# teclado_at_f343_smd_v2.net
KiCad netlist of a schematic drawn in EAGLE
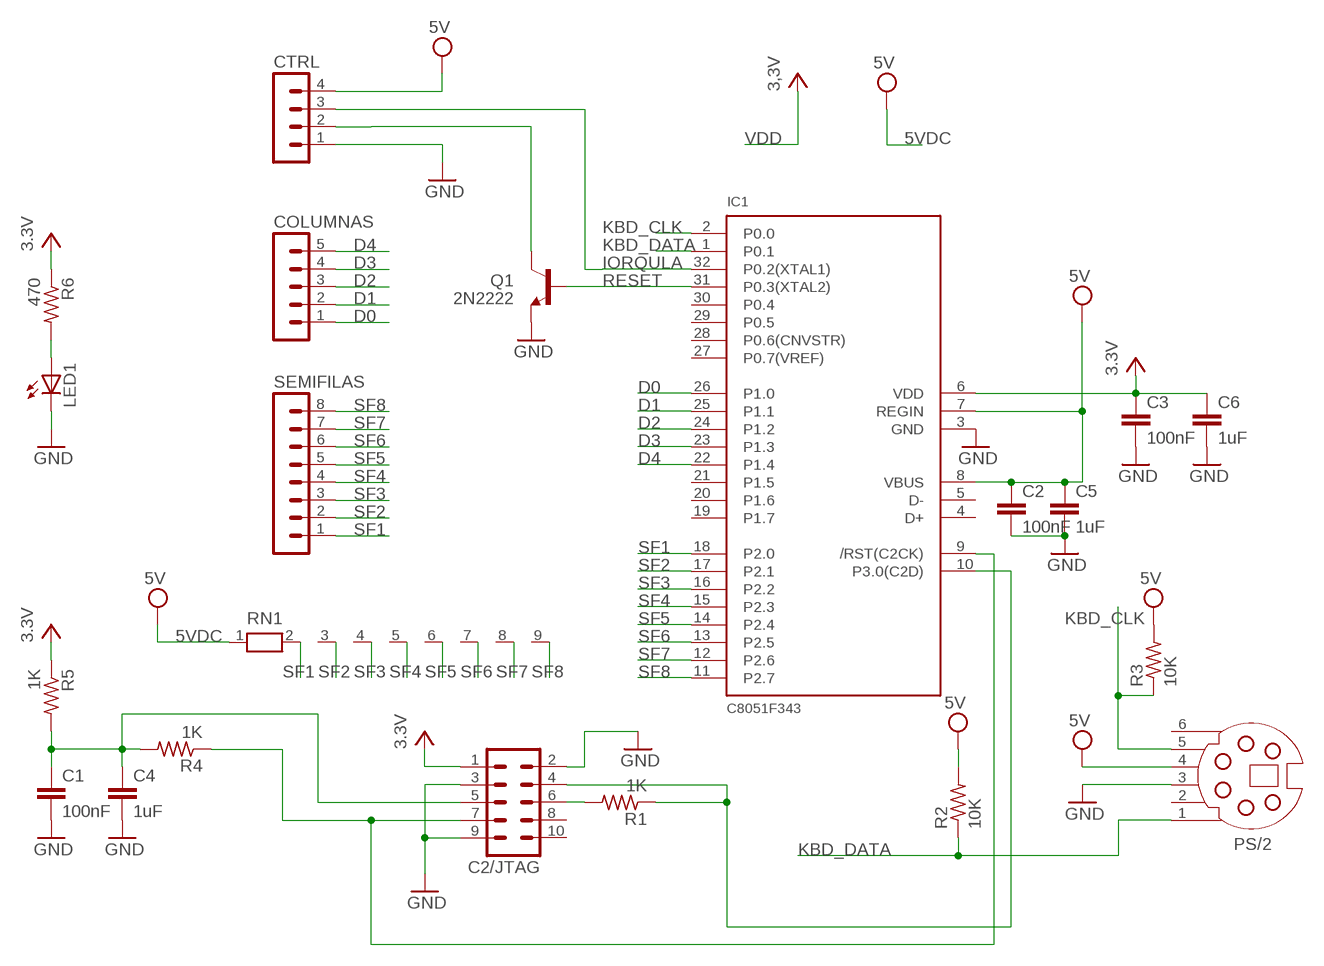
[diagram p0: schematic, sheet 1]

(export (version "E")
  (design (tool "Eeschema 10.0.6"))
  (components
    (comp (ref "C1")
      (value "100nF")
      (footprint "eagle-import:C0805K")
      (libsource (lib "eagle-import") (part "C-EUC0805K"))
    )
    (comp (ref "C2")
      (value "100nF")
      (footprint "eagle-import:C0805K")
      (libsource (lib "eagle-import") (part "C-EUC0805K"))
    )
    (comp (ref "C2/JTAG")
      (value "MA05-2")
      (footprint "eagle-import:MA05-2")
      (libsource (lib "eagle-import") (part "MA05-2"))
    )
    (comp (ref "C3")
      (value "100nF")
      (footprint "eagle-import:C0805K")
      (libsource (lib "eagle-import") (part "C-EUC0805K"))
    )
    (comp (ref "C4")
      (value "1uF")
      (footprint "eagle-import:C0805K")
      (libsource (lib "eagle-import") (part "C-EUC0805K"))
    )
    (comp (ref "C5")
      (value "1uF")
      (footprint "eagle-import:C0805K")
      (libsource (lib "eagle-import") (part "C-EUC0805K"))
    )
    (comp (ref "C6")
      (value "1uF")
      (footprint "eagle-import:C0805K")
      (libsource (lib "eagle-import") (part "C-EUC0805K"))
    )
    (comp (ref "COLUMNAS")
      (value "MA05-1")
      (footprint "eagle-import:MA05-1")
      (libsource (lib "eagle-import") (part "MA05-1"))
    )
    (comp (ref "CTRL")
      (value "MA04-1")
      (footprint "eagle-import:MA04-1")
      (libsource (lib "eagle-import") (part "MA04-1"))
    )
    (comp (ref "IC1")
      (value "C8051F343")
      (footprint "eagle-import:TQFP32-08")
      (libsource (lib "eagle-import") (part "C8051F343"))
    )
    (comp (ref "LED1")
      (value "LEDCHIP-LED0805")
      (footprint "eagle-import:CHIP-LED0805")
      (libsource (lib "eagle-import") (part "LEDCHIP-LED0805"))
    )
    (comp (ref "PS/2")
      (value "SSV-G06")
      (footprint "eagle-import:SSV-BC06")
      (libsource (lib "eagle-import") (part "SSV-G06"))
    )
    (comp (ref "Q1")
      (value "2N2222")
      (footprint "eagle-import:SOT23-3")
      (libsource (lib "eagle-import") (part "TRANSISTOR_NPNSOT23-3"))
    )
    (comp (ref "R1")
      (value "1K")
      (footprint "eagle-import:M0805")
      (libsource (lib "eagle-import") (part "R-US_M0805"))
    )
    (comp (ref "R2")
      (value "10K")
      (footprint "eagle-import:M0805")
      (libsource (lib "eagle-import") (part "R-US_M0805"))
    )
    (comp (ref "R3")
      (value "10K")
      (footprint "eagle-import:M0805")
      (libsource (lib "eagle-import") (part "R-US_M0805"))
    )
    (comp (ref "R4")
      (value "1K")
      (footprint "eagle-import:M0805")
      (libsource (lib "eagle-import") (part "R-US_M0805"))
    )
    (comp (ref "R5")
      (value "1K")
      (footprint "eagle-import:M0805")
      (libsource (lib "eagle-import") (part "R-US_M0805"))
    )
    (comp (ref "R6")
      (value "470")
      (footprint "eagle-import:M0805")
      (libsource (lib "eagle-import") (part "R-US_M0805"))
    )
    (comp (ref "RN1")
      (value "RN08")
      (footprint "eagle-import:RN-9")
      (libsource (lib "eagle-import") (part "RN08"))
    )
    (comp (ref "SEMIFILAS")
      (value "MA08-1")
      (footprint "eagle-import:MA08-1")
      (libsource (lib "eagle-import") (part "MA08-1"))
    )
  )
  (nets
    (net (code "1") (name "/D0") (class "Default")
      (node (ref "COLUMNAS") (pin "1") (pinfunction "1_1") (pintype "passive"))
      (node (ref "IC1") (pin "26") (pinfunction "P1.0_26") (pintype "bidirectional"))
    )
    (net (code "2") (name "/D1") (class "Default")
      (node (ref "COLUMNAS") (pin "2") (pinfunction "2_2") (pintype "passive"))
      (node (ref "IC1") (pin "25") (pinfunction "P1.1_25") (pintype "bidirectional"))
    )
    (net (code "3") (name "/D2") (class "Default")
      (node (ref "COLUMNAS") (pin "3") (pinfunction "3_3") (pintype "passive"))
      (node (ref "IC1") (pin "24") (pinfunction "P1.2_24") (pintype "bidirectional"))
    )
    (net (code "4") (name "/D3") (class "Default")
      (node (ref "COLUMNAS") (pin "4") (pinfunction "4_4") (pintype "passive"))
      (node (ref "IC1") (pin "23") (pinfunction "P1.3_23") (pintype "bidirectional"))
    )
    (net (code "5") (name "/D4") (class "Default")
      (node (ref "COLUMNAS") (pin "5") (pinfunction "5_5") (pintype "passive"))
      (node (ref "IC1") (pin "22") (pinfunction "P1.4_22") (pintype "bidirectional"))
    )
    (net (code "6") (name "/IORQULA") (class "Default")
      (node (ref "CTRL") (pin "3") (pinfunction "3_3") (pintype "passive"))
      (node (ref "IC1") (pin "32") (pinfunction "P0.2(XTAL1)_32") (pintype "bidirectional"))
    )
    (net (code "7") (name "/KBD_CLK") (class "Default")
      (node (ref "IC1") (pin "2") (pinfunction "P0.0_2") (pintype "bidirectional"))
      (node (ref "PS/2") (pin "5") (pinfunction "5_5") (pintype "passive"))
      (node (ref "R3") (pin "1") (pinfunction "1_1") (pintype "passive"))
    )
    (net (code "8") (name "/KBD_DATA") (class "Default")
      (node (ref "IC1") (pin "1") (pinfunction "P0.1_1") (pintype "bidirectional"))
      (node (ref "PS/2") (pin "1") (pinfunction "1_1") (pintype "passive"))
      (node (ref "R2") (pin "1") (pinfunction "1_1") (pintype "passive"))
    )
    (net (code "9") (name "/RESET") (class "Default")
      (node (ref "IC1") (pin "31") (pinfunction "P0.3(XTAL2)_31") (pintype "bidirectional"))
      (node (ref "Q1") (pin "1") (pinfunction "B_1") (pintype "passive"))
    )
    (net (code "10") (name "/SF1") (class "Default")
      (node (ref "IC1") (pin "18") (pinfunction "P2.0_18") (pintype "bidirectional"))
      (node (ref "RN1") (pin "2") (pinfunction "2_2") (pintype "passive"))
      (node (ref "SEMIFILAS") (pin "1") (pinfunction "1_1") (pintype "passive"))
    )
    (net (code "11") (name "/SF2") (class "Default")
      (node (ref "IC1") (pin "17") (pinfunction "P2.1_17") (pintype "bidirectional"))
      (node (ref "RN1") (pin "3") (pinfunction "3_3") (pintype "passive"))
      (node (ref "SEMIFILAS") (pin "2") (pinfunction "2_2") (pintype "passive"))
    )
    (net (code "12") (name "/SF3") (class "Default")
      (node (ref "IC1") (pin "16") (pinfunction "P2.2_16") (pintype "bidirectional"))
      (node (ref "RN1") (pin "4") (pinfunction "4_4") (pintype "passive"))
      (node (ref "SEMIFILAS") (pin "3") (pinfunction "3_3") (pintype "passive"))
    )
    (net (code "13") (name "/SF4") (class "Default")
      (node (ref "IC1") (pin "15") (pinfunction "P2.3_15") (pintype "bidirectional"))
      (node (ref "RN1") (pin "5") (pinfunction "5_5") (pintype "passive"))
      (node (ref "SEMIFILAS") (pin "4") (pinfunction "4_4") (pintype "passive"))
    )
    (net (code "14") (name "/SF5") (class "Default")
      (node (ref "IC1") (pin "14") (pinfunction "P2.4_14") (pintype "bidirectional"))
      (node (ref "RN1") (pin "6") (pinfunction "6_6") (pintype "passive"))
      (node (ref "SEMIFILAS") (pin "5") (pinfunction "5_5") (pintype "passive"))
    )
    (net (code "15") (name "/SF6") (class "Default")
      (node (ref "IC1") (pin "13") (pinfunction "P2.5_13") (pintype "bidirectional"))
      (node (ref "RN1") (pin "7") (pinfunction "7_7") (pintype "passive"))
      (node (ref "SEMIFILAS") (pin "6") (pinfunction "6_6") (pintype "passive"))
    )
    (net (code "16") (name "/SF7") (class "Default")
      (node (ref "IC1") (pin "12") (pinfunction "P2.6_12") (pintype "bidirectional"))
      (node (ref "RN1") (pin "8") (pinfunction "8_8") (pintype "passive"))
      (node (ref "SEMIFILAS") (pin "7") (pinfunction "7_7") (pintype "passive"))
    )
    (net (code "17") (name "/SF8") (class "Default")
      (node (ref "IC1") (pin "11") (pinfunction "P2.7_11") (pintype "bidirectional"))
      (node (ref "RN1") (pin "9") (pinfunction "9_9") (pintype "passive"))
      (node (ref "SEMIFILAS") (pin "8") (pinfunction "8_8") (pintype "passive"))
    )
    (net (code "18") (name "3,3V") (class "Default")
      (node (ref "C2/JTAG") (pin "1") (pinfunction "1_1") (pintype "passive"))
      (node (ref "C3") (pin "1") (pinfunction "1_1") (pintype "passive"))
      (node (ref "C6") (pin "1") (pinfunction "1_1") (pintype "passive"))
      (node (ref "IC1") (pin "6") (pinfunction "VDD_6") (pintype "power_in"))
      (node (ref "R5") (pin "1") (pinfunction "1_1") (pintype "passive"))
      (node (ref "R6") (pin "1") (pinfunction "1_1") (pintype "passive"))
    )
    (net (code "19") (name "5V") (class "Default")
      (node (ref "C2") (pin "1") (pinfunction "1_1") (pintype "passive"))
      (node (ref "C5") (pin "1") (pinfunction "1_1") (pintype "passive"))
      (node (ref "CTRL") (pin "4") (pinfunction "4_4") (pintype "passive"))
      (node (ref "IC1") (pin "7") (pinfunction "REGIN_7") (pintype "power_in"))
      (node (ref "IC1") (pin "8") (pinfunction "VBUS_8") (pintype "power_in"))
      (node (ref "PS/2") (pin "4") (pinfunction "4_4") (pintype "passive"))
      (node (ref "R2") (pin "2") (pinfunction "2_2") (pintype "passive"))
      (node (ref "R3") (pin "2") (pinfunction "2_2") (pintype "passive"))
      (node (ref "RN1") (pin "1") (pinfunction "1_1") (pintype "passive"))
    )
    (net (code "20") (name "GND") (class "Default")
      (node (ref "C1") (pin "2") (pinfunction "2_2") (pintype "passive"))
      (node (ref "C2") (pin "2") (pinfunction "2_2") (pintype "passive"))
      (node (ref "C2/JTAG") (pin "2") (pinfunction "2_2") (pintype "passive"))
      (node (ref "C2/JTAG") (pin "3") (pinfunction "3_3") (pintype "passive"))
      (node (ref "C2/JTAG") (pin "9") (pinfunction "9_9") (pintype "passive"))
      (node (ref "C3") (pin "2") (pinfunction "2_2") (pintype "passive"))
      (node (ref "C4") (pin "2") (pinfunction "2_2") (pintype "passive"))
      (node (ref "C5") (pin "2") (pinfunction "2_2") (pintype "passive"))
      (node (ref "C6") (pin "2") (pinfunction "2_2") (pintype "passive"))
      (node (ref "CTRL") (pin "1") (pinfunction "1_1") (pintype "passive"))
      (node (ref "IC1") (pin "3") (pinfunction "GND_3") (pintype "power_in"))
      (node (ref "LED1") (pin "C") (pinfunction "C_C") (pintype "passive"))
      (node (ref "PS/2") (pin "3") (pinfunction "3_3") (pintype "passive"))
      (node (ref "Q1") (pin "2") (pinfunction "E_2") (pintype "passive"))
    )
    (net (code "21") (name "Net-(C1-Pad1)") (class "Default")
      (node (ref "C1") (pin "1") (pinfunction "1_1") (pintype "passive"))
      (node (ref "C2/JTAG") (pin "5") (pinfunction "5_5") (pintype "passive"))
      (node (ref "C4") (pin "1") (pinfunction "1_1") (pintype "passive"))
      (node (ref "R4") (pin "2") (pinfunction "2_2") (pintype "passive"))
      (node (ref "R5") (pin "2") (pinfunction "2_2") (pintype "passive"))
    )
    (net (code "22") (name "Net-(C2/JTAG-Pad6)") (class "Default")
      (node (ref "C2/JTAG") (pin "6") (pinfunction "6_6") (pintype "passive"))
      (node (ref "R1") (pin "2") (pinfunction "2_2") (pintype "passive"))
    )
    (net (code "23") (name "Net-(IC1-P3.0(C2D))") (class "Default")
      (node (ref "C2/JTAG") (pin "4") (pinfunction "4_4") (pintype "passive"))
      (node (ref "IC1") (pin "10") (pinfunction "P3.0(C2D)_10") (pintype "bidirectional"))
      (node (ref "R1") (pin "1") (pinfunction "1_1") (pintype "passive"))
    )
    (net (code "24") (name "Net-(IC1-{slash}RST(C2CK))") (class "Default")
      (node (ref "C2/JTAG") (pin "7") (pinfunction "7_7") (pintype "passive"))
      (node (ref "IC1") (pin "9") (pinfunction "/RST(C2CK)_9") (pintype "bidirectional"))
      (node (ref "R4") (pin "1") (pinfunction "1_1") (pintype "passive"))
    )
    (net (code "25") (name "Net-(LED1-PadA)") (class "Default")
      (node (ref "LED1") (pin "A") (pinfunction "A_A") (pintype "passive"))
      (node (ref "R6") (pin "2") (pinfunction "2_2") (pintype "passive"))
    )
    (net (code "26") (name "Net-(Q1-C)") (class "Default")
      (node (ref "CTRL") (pin "2") (pinfunction "2_2") (pintype "passive"))
      (node (ref "Q1") (pin "3") (pinfunction "C_3") (pintype "passive"))
    )
    (net (code "27") (name "unconnected-(C2/JTAG-Pad8)") (class "Default")
      (node (ref "C2/JTAG") (pin "8") (pinfunction "8_8") (pintype "passive"))
    )
    (net (code "28") (name "unconnected-(C2/JTAG-Pad10)") (class "Default")
      (node (ref "C2/JTAG") (pin "10") (pinfunction "10_10") (pintype "passive"))
    )
    (net (code "29") (name "unconnected-(IC1-D+-Pad4)") (class "Default")
      (node (ref "IC1") (pin "4") (pinfunction "D+_4") (pintype "bidirectional"))
    )
    (net (code "30") (name "unconnected-(IC1-D--Pad5)") (class "Default")
      (node (ref "IC1") (pin "5") (pinfunction "D-_5") (pintype "bidirectional"))
    )
    (net (code "31") (name "unconnected-(IC1-P0.4-Pad30)") (class "Default")
      (node (ref "IC1") (pin "30") (pinfunction "P0.4_30") (pintype "bidirectional"))
    )
    (net (code "32") (name "unconnected-(IC1-P0.5-Pad29)") (class "Default")
      (node (ref "IC1") (pin "29") (pinfunction "P0.5_29") (pintype "bidirectional"))
    )
    (net (code "33") (name "unconnected-(IC1-P0.6(CNVSTR)-Pad28)") (class "Default")
      (node (ref "IC1") (pin "28") (pinfunction "P0.6(CNVSTR)_28") (pintype "bidirectional"))
    )
    (net (code "34") (name "unconnected-(IC1-P0.7(VREF)-Pad27)") (class "Default")
      (node (ref "IC1") (pin "27") (pinfunction "P0.7(VREF)_27") (pintype "bidirectional"))
    )
    (net (code "35") (name "unconnected-(IC1-P1.5-Pad21)") (class "Default")
      (node (ref "IC1") (pin "21") (pinfunction "P1.5_21") (pintype "bidirectional"))
    )
    (net (code "36") (name "unconnected-(IC1-P1.6-Pad20)") (class "Default")
      (node (ref "IC1") (pin "20") (pinfunction "P1.6_20") (pintype "bidirectional"))
    )
    (net (code "37") (name "unconnected-(IC1-P1.7-Pad19)") (class "Default")
      (node (ref "IC1") (pin "19") (pinfunction "P1.7_19") (pintype "bidirectional"))
    )
    (net (code "38") (name "unconnected-(PS/2-Pad2)") (class "Default")
      (node (ref "PS/2") (pin "2") (pinfunction "2_2") (pintype "passive"))
    )
    (net (code "39") (name "unconnected-(PS/2-Pad6)") (class "Default")
      (node (ref "PS/2") (pin "6") (pinfunction "6_6") (pintype "passive"))
    )
  )
)
